# Bioscope-Input-01.net
KiCad netlist of a schematic drawn in Altium Designer
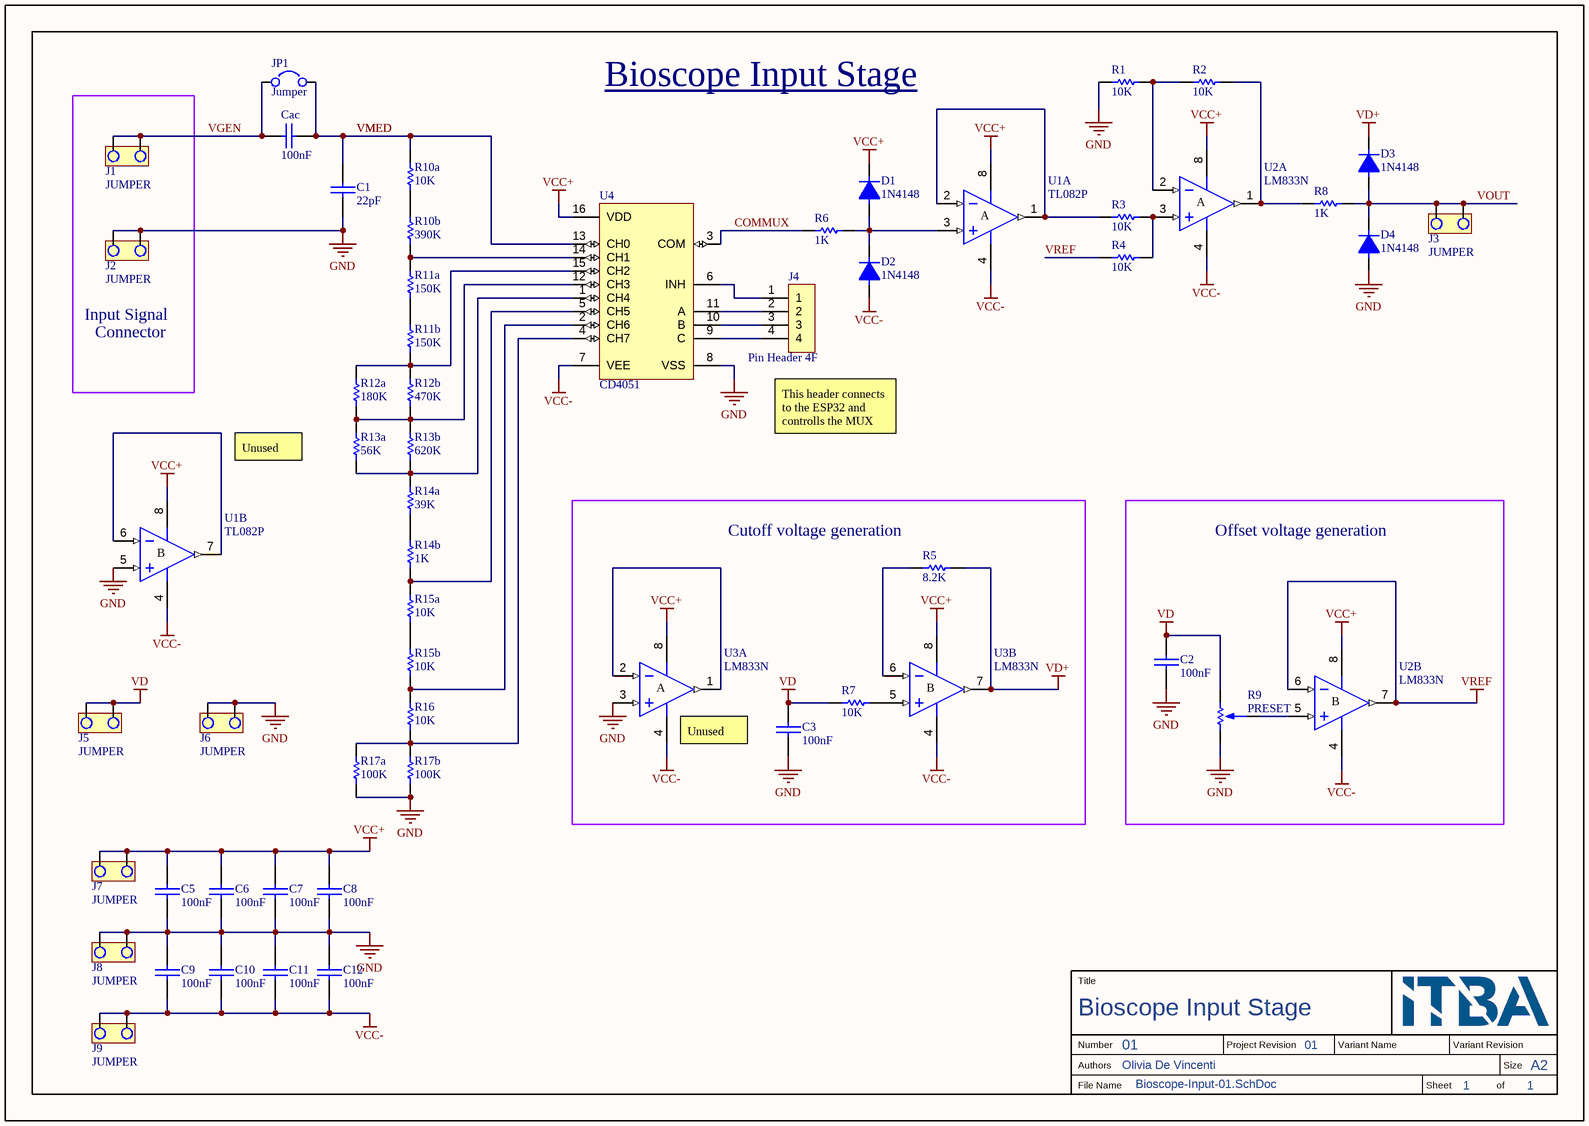
[diagram p0: Bioscope-Input-01.SchDoc]

(export (version "E")
  (design (tool "Eeschema 10.0.6"))
  (components
    (comp (ref "C1") (value "22pF") (footprint "CAP100") (libsource (lib "LIBEBAL") (part "CAP")))
    (comp (ref "C2") (value "100nF") (footprint "CAP100") (libsource (lib "LIBEBAL") (part "CAP")))
    (comp (ref "C3") (value "100nF") (footprint "CAP200") (libsource (lib "LIBEBAL") (part "CAP")))
    (comp (ref "C5") (value "100nF") (footprint "CAP100") (libsource (lib "LIBEBAL") (part "CAP")))
    (comp (ref "C6") (value "100nF") (footprint "CAP100") (libsource (lib "LIBEBAL") (part "CAP")))
    (comp (ref "C7") (value "100nF") (footprint "CAP100") (libsource (lib "LIBEBAL") (part "CAP")))
    (comp (ref "C8") (value "100nF") (footprint "CAP100") (libsource (lib "LIBEBAL") (part "CAP")))
    (comp (ref "C9") (value "100nF") (footprint "CAP100") (libsource (lib "LIBEBAL") (part "CAP")))
    (comp (ref "C10") (value "100nF") (footprint "CAP200") (libsource (lib "LIBEBAL") (part "CAP")))
    (comp (ref "C11") (value "100nF") (footprint "CAP100") (libsource (lib "LIBEBAL") (part "CAP")))
    (comp (ref "C12") (value "100nF") (footprint "CAP100") (libsource (lib "LIBEBAL") (part "CAP")))
    (comp (ref "Cac") (value "100nF") (footprint "CAP100") (libsource (lib "LIBEBAL") (part "CAP")))
    (comp (ref "D1") (value "1N4148") (footprint "DO41") (libsource (lib "LIBEBAL") (part "DIODO")))
    (comp (ref "D2") (value "1N4148") (footprint "DO41") (libsource (lib "LIBEBAL") (part "DIODO")))
    (comp (ref "D3") (value "1N4148") (footprint "DO41") (libsource (lib "LIBEBAL") (part "DIODO")))
    (comp (ref "D4") (value "1N4148") (footprint "DO41") (libsource (lib "LIBEBAL") (part "DIODO")))
    (comp (ref "J1") (value "JUMPER") (footprint "JUMPER2") (libsource (lib "LIBEBAL") (part "JUMPER")))
    (comp (ref "J2") (value "JUMPER") (footprint "JUMPER2") (libsource (lib "LIBEBAL") (part "JUMPER")))
    (comp (ref "J3") (value "JUMPER") (footprint "JUMPER2") (libsource (lib "LIBEBAL") (part "JUMPER")))
    (comp (ref "J4")
      (value "Pin Header 4F")
      (footprint "PINHEADER-4F")
      (description "Pin Header, Female, 4 positions")
      (libsource (lib "BIOSCOPE-LIB") (part "PINHEADER-4F"))
    )
    (comp (ref "J5") (value "JUMPER") (footprint "JUMPER2") (libsource (lib "LIBEBAL") (part "JUMPER")))
    (comp (ref "J6") (value "JUMPER") (footprint "JUMPER2") (libsource (lib "LIBEBAL") (part "JUMPER")))
    (comp (ref "J7") (value "JUMPER") (footprint "JUMPER2") (libsource (lib "LIBEBAL") (part "JUMPER")))
    (comp (ref "J8") (value "JUMPER") (footprint "JUMPER2") (libsource (lib "LIBEBAL") (part "JUMPER")))
    (comp (ref "J9") (value "JUMPER") (footprint "JUMPER2") (libsource (lib "LIBEBAL") (part "JUMPER")))
    (comp (ref "JP1")
      (value "Jumper")
      (footprint "JUMPER-HEADER")
      (description "2.54mm 2 pin header and jumper")
      (libsource (lib "BIOSCOPE-LIB") (part "Jumper Header"))
    )
    (comp (ref "R1") (value "10K") (footprint "RES400") (libsource (lib "LIBEBAL") (part "RES")))
    (comp (ref "R2") (value "10K") (footprint "RES400") (libsource (lib "LIBEBAL") (part "RES")))
    (comp (ref "R3") (value "10K") (footprint "RES400") (libsource (lib "LIBEBAL") (part "RES")))
    (comp (ref "R4") (value "10K") (footprint "RES400") (libsource (lib "LIBEBAL") (part "RES")))
    (comp (ref "R5") (value "8.2K") (footprint "RES400") (libsource (lib "LIBEBAL") (part "RES")))
    (comp (ref "R6") (value "1K") (footprint "RES400") (libsource (lib "LIBEBAL") (part "RES")))
    (comp (ref "R7") (value "10K") (footprint "RES400") (libsource (lib "LIBEBAL") (part "RES")))
    (comp (ref "R8") (value "1K") (footprint "RES400") (libsource (lib "LIBEBAL") (part "RES")))
    (comp (ref "R9") (value "PRESET") (footprint "PRESET V") (libsource (lib "LIBEBAL") (part "PRESET")))
    (comp (ref "R10a") (value "10K") (footprint "RES400") (libsource (lib "LIBEBAL") (part "RES")))
    (comp (ref "R10b") (value "390K") (footprint "RES400") (libsource (lib "LIBEBAL") (part "RES")))
    (comp (ref "R11a") (value "150K") (footprint "RES400") (libsource (lib "LIBEBAL") (part "RES")))
    (comp (ref "R11b") (value "150K") (footprint "RES400") (libsource (lib "LIBEBAL") (part "RES")))
    (comp (ref "R12a") (value "180K") (footprint "RES400") (libsource (lib "LIBEBAL") (part "RES")))
    (comp (ref "R12b") (value "470K") (footprint "RES400") (libsource (lib "LIBEBAL") (part "RES")))
    (comp (ref "R13a") (value "56K") (footprint "RES400") (libsource (lib "LIBEBAL") (part "RES")))
    (comp (ref "R13b") (value "620K") (footprint "RES400") (libsource (lib "LIBEBAL") (part "RES")))
    (comp (ref "R14a") (value "39K") (footprint "RES400") (libsource (lib "LIBEBAL") (part "RES")))
    (comp (ref "R14b") (value "1K") (footprint "RES400") (libsource (lib "LIBEBAL") (part "RES")))
    (comp (ref "R15a") (value "10K") (footprint "RES400") (libsource (lib "LIBEBAL") (part "RES")))
    (comp (ref "R15b") (value "10K") (footprint "RES400") (libsource (lib "LIBEBAL") (part "RES")))
    (comp (ref "R16") (value "10K") (footprint "RES400") (libsource (lib "LIBEBAL") (part "RES")))
    (comp (ref "R17a") (value "100K") (footprint "RES400") (libsource (lib "LIBEBAL") (part "RES")))
    (comp (ref "R17b") (value "100K") (footprint "RES400") (libsource (lib "LIBEBAL") (part "RES")))
    (comp (ref "U1")
      (value "TL082P")
      (footprint "P008")
      (description "JFET-Input Operational Amplifier")
      (fields (field (name "PUBLISHER") "Altium Limited"))
      (libsource (lib "TI Operational Amplifier") (part "TL082P"))
    )
    (comp (ref "U2")
      (value "LM833N")
      (footprint "DIP8")
      (description "Low-Noise Dual Operational Amplifier")
      (fields (field (name "PUBLISHER") "Altium Limited"))
      (libsource (lib "ST Operational Amplifier") (part "LM833N"))
    )
    (comp (ref "U3")
      (value "LM833N")
      (footprint "DIP8")
      (description "Low-Noise Dual Operational Amplifier")
      (fields (field (name "PUBLISHER") "Altium Limited"))
      (libsource (lib "ST Operational Amplifier") (part "LM833N"))
    )
    (comp (ref "U4")
      (value "CD4051")
      (footprint "SOIC16")
      (description "Single 8-Channel Analog Multiplexer or Demultiplexer")
      (libsource (lib "BIOSCOPE-LIB") (part "CD4051BF"))
    )
  )
  (nets
    (net (code "1") (name "/COMMUX") (class "Default")
      (node (ref "R6") (pin "1") (pinfunction "1_1") (pintype "passive"))
      (node (ref "U4") (pin "3") (pinfunction "COM_3") (pintype "bidirectional"))
    )
    (net (code "2") (name "/VGEN") (class "Default")
      (node (ref "Cac") (pin "1") (pinfunction "1_1") (pintype "passive"))
      (node (ref "J1") (pin "1") (pinfunction "1_1") (pintype "passive"))
      (node (ref "J1") (pin "2") (pinfunction "2_2") (pintype "passive"))
      (node (ref "JP1") (pin "1") (pinfunction "1_1") (pintype "passive"))
    )
    (net (code "3") (name "/VMED") (class "Default")
      (node (ref "C1") (pin "1") (pinfunction "1_1") (pintype "passive"))
      (node (ref "Cac") (pin "2") (pinfunction "2_2") (pintype "passive"))
      (node (ref "JP1") (pin "2") (pinfunction "2_2") (pintype "passive"))
      (node (ref "R10a") (pin "2") (pinfunction "2_2") (pintype "passive"))
      (node (ref "U4") (pin "13") (pinfunction "CH0_13") (pintype "bidirectional"))
    )
    (net (code "4") (name "/VOUT") (class "Default")
      (node (ref "D3") (pin "1") (pinfunction "1_1") (pintype "passive"))
      (node (ref "D4") (pin "2") (pinfunction "2_2") (pintype "passive"))
      (node (ref "J3") (pin "1") (pinfunction "1_1") (pintype "passive"))
      (node (ref "J3") (pin "2") (pinfunction "2_2") (pintype "passive"))
      (node (ref "R8") (pin "2") (pinfunction "2_2") (pintype "passive"))
    )
    (net (code "5") (name "GND") (class "Default")
      (node (ref "C1") (pin "2") (pinfunction "2_2") (pintype "passive"))
      (node (ref "C10") (pin "1") (pinfunction "1_1") (pintype "passive"))
      (node (ref "C11") (pin "1") (pinfunction "1_1") (pintype "passive"))
      (node (ref "C12") (pin "1") (pinfunction "1_1") (pintype "passive"))
      (node (ref "C2") (pin "2") (pinfunction "2_2") (pintype "passive"))
      (node (ref "C3") (pin "2") (pinfunction "2_2") (pintype "passive"))
      (node (ref "C5") (pin "2") (pinfunction "2_2") (pintype "passive"))
      (node (ref "C6") (pin "2") (pinfunction "2_2") (pintype "passive"))
      (node (ref "C7") (pin "2") (pinfunction "2_2") (pintype "passive"))
      (node (ref "C8") (pin "2") (pinfunction "2_2") (pintype "passive"))
      (node (ref "C9") (pin "1") (pinfunction "1_1") (pintype "passive"))
      (node (ref "D4") (pin "1") (pinfunction "1_1") (pintype "passive"))
      (node (ref "J2") (pin "1") (pinfunction "1_1") (pintype "passive"))
      (node (ref "J2") (pin "2") (pinfunction "2_2") (pintype "passive"))
      (node (ref "J6") (pin "1") (pinfunction "1_1") (pintype "passive"))
      (node (ref "J6") (pin "2") (pinfunction "2_2") (pintype "passive"))
      (node (ref "J8") (pin "1") (pinfunction "1_1") (pintype "passive"))
      (node (ref "J8") (pin "2") (pinfunction "2_2") (pintype "passive"))
      (node (ref "R1") (pin "1") (pinfunction "1_1") (pintype "passive"))
      (node (ref "R17a") (pin "1") (pinfunction "1_1") (pintype "passive"))
      (node (ref "R17b") (pin "1") (pinfunction "1_1") (pintype "passive"))
      (node (ref "R9") (pin "3") (pinfunction "3_3") (pintype "passive"))
      (node (ref "U1") (pin "5") (pinfunction "IN+_5") (pintype "input"))
      (node (ref "U3") (pin "3") (pinfunction "IN+_3") (pintype "input"))
      (node (ref "U4") (pin "8") (pinfunction "VSS_8") (pintype "passive"))
    )
    (net (code "6") (name "Net-(R10a-Pad1)") (class "Default")
      (node (ref "R10a") (pin "1") (pinfunction "1_1") (pintype "passive"))
      (node (ref "R10b") (pin "2") (pinfunction "2_2") (pintype "passive"))
    )
    (net (code "7") (name "Net-(R11a-Pad1)") (class "Default")
      (node (ref "R11a") (pin "1") (pinfunction "1_1") (pintype "passive"))
      (node (ref "R11b") (pin "2") (pinfunction "2_2") (pintype "passive"))
    )
    (net (code "8") (name "Net-(R14a-Pad1)") (class "Default")
      (node (ref "R14a") (pin "1") (pinfunction "1_1") (pintype "passive"))
      (node (ref "R14b") (pin "2") (pinfunction "2_2") (pintype "passive"))
    )
    (net (code "9") (name "Net-(R15a-Pad1)") (class "Default")
      (node (ref "R15a") (pin "1") (pinfunction "1_1") (pintype "passive"))
      (node (ref "R15b") (pin "2") (pinfunction "2_2") (pintype "passive"))
    )
    (net (code "10") (name "Net-(U1A-IN+)") (class "Default")
      (node (ref "D1") (pin "1") (pinfunction "1_1") (pintype "passive"))
      (node (ref "D2") (pin "2") (pinfunction "2_2") (pintype "passive"))
      (node (ref "R6") (pin "2") (pinfunction "2_2") (pintype "passive"))
      (node (ref "U1") (pin "3") (pinfunction "IN+_3") (pintype "input"))
    )
    (net (code "11") (name "Net-(U1A-IN-)") (class "Default")
      (node (ref "R3") (pin "1") (pinfunction "1_1") (pintype "passive"))
      (node (ref "U1") (pin "1") (pinfunction "OUT_1") (pintype "output"))
      (node (ref "U1") (pin "2") (pinfunction "IN-_2") (pintype "input"))
    )
    (net (code "12") (name "Net-(U1B-IN-)") (class "Default")
      (node (ref "U1") (pin "6") (pinfunction "IN-_6") (pintype "input"))
      (node (ref "U1") (pin "7") (pinfunction "OUT_7") (pintype "output"))
    )
    (net (code "13") (name "Net-(U2A-IN+)") (class "Default")
      (node (ref "R3") (pin "2") (pinfunction "2_2") (pintype "passive"))
      (node (ref "R4") (pin "2") (pinfunction "2_2") (pintype "passive"))
      (node (ref "U2") (pin "3") (pinfunction "IN+_3") (pintype "input"))
    )
    (net (code "14") (name "Net-(U2A-IN-)") (class "Default")
      (node (ref "R1") (pin "2") (pinfunction "2_2") (pintype "passive"))
      (node (ref "R2") (pin "1") (pinfunction "1_1") (pintype "passive"))
      (node (ref "U2") (pin "2") (pinfunction "IN-_2") (pintype "input"))
    )
    (net (code "15") (name "Net-(U2A-OUT)") (class "Default")
      (node (ref "R2") (pin "2") (pinfunction "2_2") (pintype "passive"))
      (node (ref "R8") (pin "1") (pinfunction "1_1") (pintype "passive"))
      (node (ref "U2") (pin "1") (pinfunction "OUT_1") (pintype "output"))
    )
    (net (code "16") (name "Net-(U2B-IN+)") (class "Default")
      (node (ref "R9") (pin "2") (pinfunction "2_2") (pintype "passive"))
      (node (ref "U2") (pin "5") (pinfunction "IN+_5") (pintype "input"))
    )
    (net (code "17") (name "Net-(U3A-IN-)") (class "Default")
      (node (ref "U3") (pin "1") (pinfunction "OUT_1") (pintype "output"))
      (node (ref "U3") (pin "2") (pinfunction "IN-_2") (pintype "input"))
    )
    (net (code "18") (name "Net-(U3B-IN+)") (class "Default")
      (node (ref "R7") (pin "2") (pinfunction "2_2") (pintype "passive"))
      (node (ref "U3") (pin "5") (pinfunction "IN+_5") (pintype "input"))
    )
    (net (code "19") (name "Net-(U3B-IN-)") (class "Default")
      (node (ref "R5") (pin "1") (pinfunction "1_1") (pintype "passive"))
      (node (ref "U3") (pin "6") (pinfunction "IN-_6") (pintype "input"))
    )
    (net (code "20") (name "Net-(U4-A)") (class "Default")
      (node (ref "J4") (pin "2") (pinfunction "2_2") (pintype "passive"))
      (node (ref "U4") (pin "11") (pinfunction "A_11") (pintype "passive"))
    )
    (net (code "21") (name "Net-(U4-B)") (class "Default")
      (node (ref "J4") (pin "3") (pinfunction "3_3") (pintype "passive"))
      (node (ref "U4") (pin "10") (pinfunction "B_10") (pintype "passive"))
    )
    (net (code "22") (name "Net-(U4-C)") (class "Default")
      (node (ref "J4") (pin "4") (pinfunction "4_4") (pintype "passive"))
      (node (ref "U4") (pin "9") (pinfunction "C_9") (pintype "passive"))
    )
    (net (code "23") (name "Net-(U4-CH1)") (class "Default")
      (node (ref "R10b") (pin "1") (pinfunction "1_1") (pintype "passive"))
      (node (ref "R11a") (pin "2") (pinfunction "2_2") (pintype "passive"))
      (node (ref "U4") (pin "14") (pinfunction "CH1_14") (pintype "bidirectional"))
    )
    (net (code "24") (name "Net-(U4-CH2)") (class "Default")
      (node (ref "R11b") (pin "1") (pinfunction "1_1") (pintype "passive"))
      (node (ref "R12a") (pin "2") (pinfunction "2_2") (pintype "passive"))
      (node (ref "R12b") (pin "2") (pinfunction "2_2") (pintype "passive"))
      (node (ref "U4") (pin "15") (pinfunction "CH2_15") (pintype "bidirectional"))
    )
    (net (code "25") (name "Net-(U4-CH3)") (class "Default")
      (node (ref "R12a") (pin "1") (pinfunction "1_1") (pintype "passive"))
      (node (ref "R12b") (pin "1") (pinfunction "1_1") (pintype "passive"))
      (node (ref "R13a") (pin "2") (pinfunction "2_2") (pintype "passive"))
      (node (ref "R13b") (pin "2") (pinfunction "2_2") (pintype "passive"))
      (node (ref "U4") (pin "12") (pinfunction "CH3_12") (pintype "bidirectional"))
    )
    (net (code "26") (name "Net-(U4-CH4)") (class "Default")
      (node (ref "R13a") (pin "1") (pinfunction "1_1") (pintype "passive"))
      (node (ref "R13b") (pin "1") (pinfunction "1_1") (pintype "passive"))
      (node (ref "R14a") (pin "2") (pinfunction "2_2") (pintype "passive"))
      (node (ref "U4") (pin "1") (pinfunction "CH4_1") (pintype "bidirectional"))
    )
    (net (code "27") (name "Net-(U4-CH5)") (class "Default")
      (node (ref "R14b") (pin "1") (pinfunction "1_1") (pintype "passive"))
      (node (ref "R15a") (pin "2") (pinfunction "2_2") (pintype "passive"))
      (node (ref "U4") (pin "5") (pinfunction "CH5_5") (pintype "bidirectional"))
    )
    (net (code "28") (name "Net-(U4-CH6)") (class "Default")
      (node (ref "R15b") (pin "1") (pinfunction "1_1") (pintype "passive"))
      (node (ref "R16") (pin "2") (pinfunction "2_2") (pintype "passive"))
      (node (ref "U4") (pin "2") (pinfunction "CH6_2") (pintype "bidirectional"))
    )
    (net (code "29") (name "Net-(U4-CH7)") (class "Default")
      (node (ref "R16") (pin "1") (pinfunction "1_1") (pintype "passive"))
      (node (ref "R17a") (pin "2") (pinfunction "2_2") (pintype "passive"))
      (node (ref "R17b") (pin "2") (pinfunction "2_2") (pintype "passive"))
      (node (ref "U4") (pin "4") (pinfunction "CH7_4") (pintype "bidirectional"))
    )
    (net (code "30") (name "Net-(U4-INH)") (class "Default")
      (node (ref "J4") (pin "1") (pinfunction "1_1") (pintype "passive"))
      (node (ref "U4") (pin "6") (pinfunction "INH_6") (pintype "passive"))
    )
    (net (code "31") (name "VCC+") (class "Default")
      (node (ref "C5") (pin "1") (pinfunction "1_1") (pintype "passive"))
      (node (ref "C6") (pin "1") (pinfunction "1_1") (pintype "passive"))
      (node (ref "C7") (pin "1") (pinfunction "1_1") (pintype "passive"))
      (node (ref "C8") (pin "1") (pinfunction "1_1") (pintype "passive"))
      (node (ref "D1") (pin "2") (pinfunction "2_2") (pintype "passive"))
      (node (ref "J7") (pin "1") (pinfunction "1_1") (pintype "passive"))
      (node (ref "J7") (pin "2") (pinfunction "2_2") (pintype "passive"))
      (node (ref "U1") (pin "8") (pinfunction "V+_8") (pintype "power_in"))
      (node (ref "U2") (pin "8") (pinfunction "V+_8") (pintype "power_in"))
      (node (ref "U3") (pin "8") (pinfunction "V+_8") (pintype "power_in"))
      (node (ref "U4") (pin "16") (pinfunction "VDD_16") (pintype "power_in"))
    )
    (net (code "32") (name "VCC-") (class "Default")
      (node (ref "C10") (pin "2") (pinfunction "2_2") (pintype "passive"))
      (node (ref "C11") (pin "2") (pinfunction "2_2") (pintype "passive"))
      (node (ref "C12") (pin "2") (pinfunction "2_2") (pintype "passive"))
      (node (ref "C9") (pin "2") (pinfunction "2_2") (pintype "passive"))
      (node (ref "D2") (pin "1") (pinfunction "1_1") (pintype "passive"))
      (node (ref "J9") (pin "1") (pinfunction "1_1") (pintype "passive"))
      (node (ref "J9") (pin "2") (pinfunction "2_2") (pintype "passive"))
      (node (ref "U1") (pin "4") (pinfunction "V-_4") (pintype "power_in"))
      (node (ref "U2") (pin "4") (pinfunction "V-_4") (pintype "power_in"))
      (node (ref "U3") (pin "4") (pinfunction "V-_4") (pintype "power_in"))
      (node (ref "U4") (pin "7") (pinfunction "VEE_7") (pintype "power_in"))
    )
    (net (code "33") (name "VD") (class "Default")
      (node (ref "C2") (pin "1") (pinfunction "1_1") (pintype "passive"))
      (node (ref "C3") (pin "1") (pinfunction "1_1") (pintype "passive"))
      (node (ref "J5") (pin "1") (pinfunction "1_1") (pintype "passive"))
      (node (ref "J5") (pin "2") (pinfunction "2_2") (pintype "passive"))
      (node (ref "R7") (pin "1") (pinfunction "1_1") (pintype "passive"))
      (node (ref "R9") (pin "1") (pinfunction "1_1") (pintype "passive"))
    )
    (net (code "34") (name "VD+") (class "Default")
      (node (ref "D3") (pin "2") (pinfunction "2_2") (pintype "passive"))
      (node (ref "R5") (pin "2") (pinfunction "2_2") (pintype "passive"))
      (node (ref "U3") (pin "7") (pinfunction "OUT_7") (pintype "output"))
    )
    (net (code "35") (name "VREF") (class "Default")
      (node (ref "R4") (pin "1") (pinfunction "1_1") (pintype "passive"))
      (node (ref "U2") (pin "6") (pinfunction "IN-_6") (pintype "input"))
      (node (ref "U2") (pin "7") (pinfunction "OUT_7") (pintype "output"))
    )
  )
)
